# ESP01S.net
KiCad netlist of a schematic drawn in Altium Designer
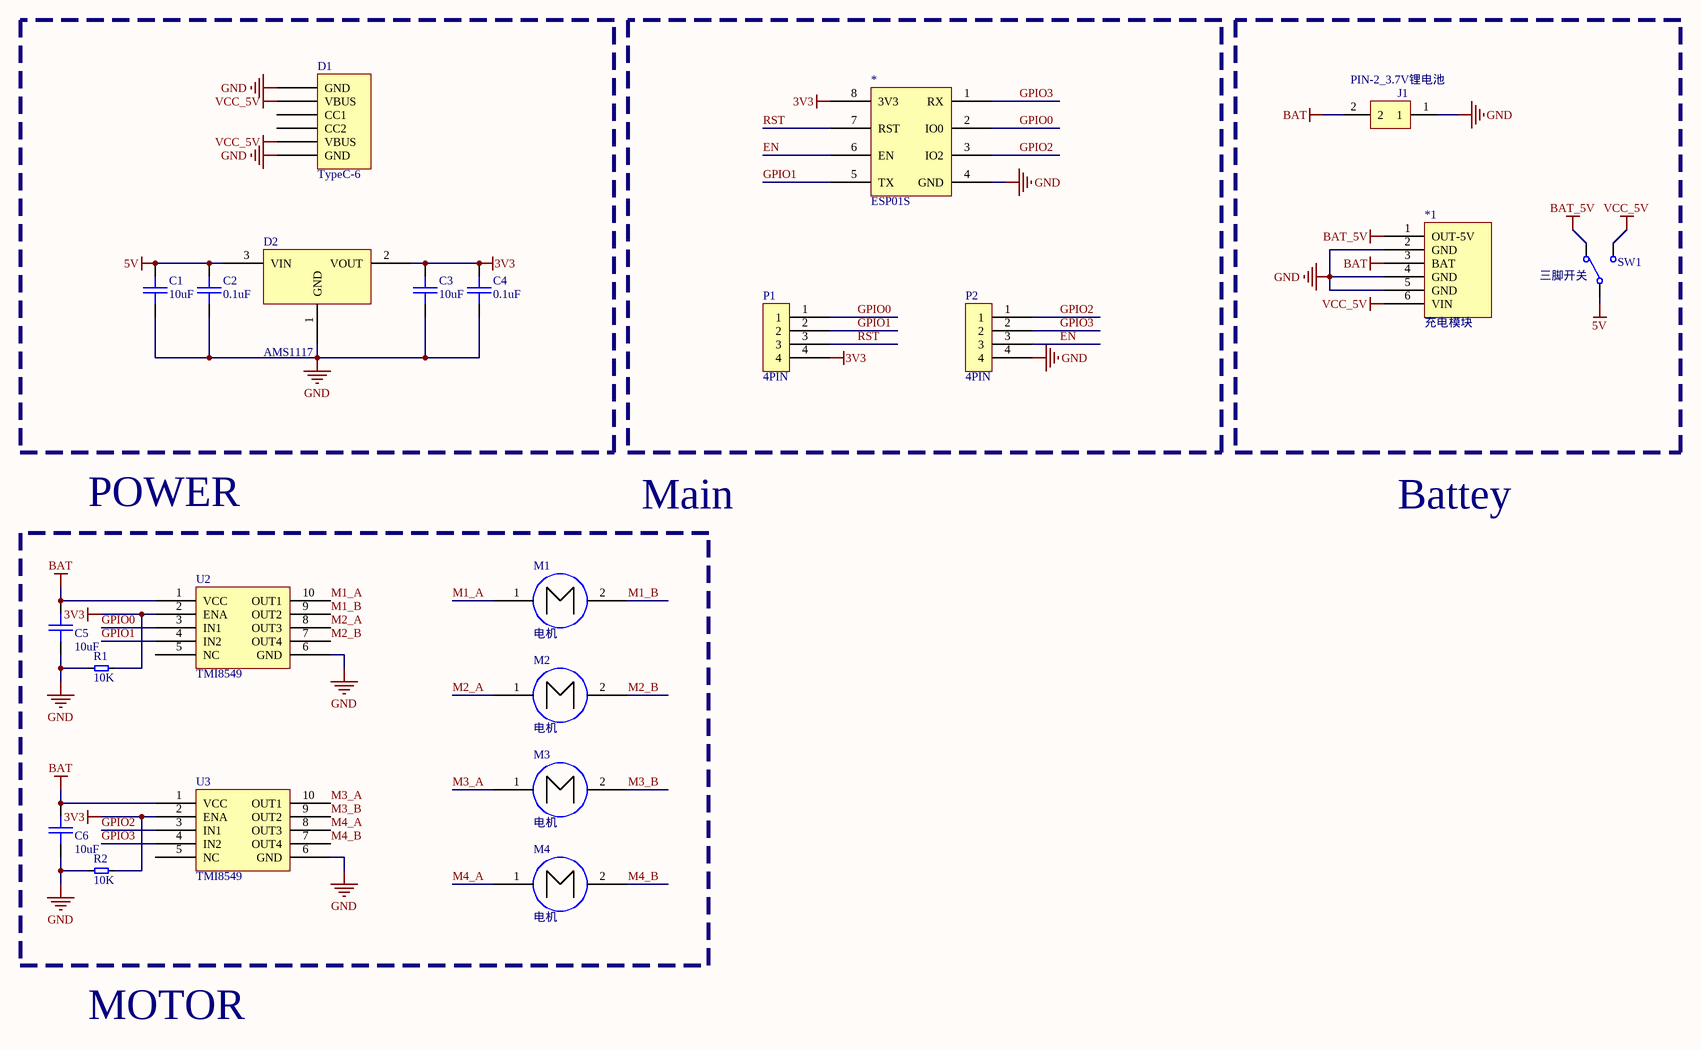
[diagram p0: ESP01S麦轮.SchDoc]

(export (version "E")
  (design (tool "Eeschema 10.0.6"))
  (components
    (comp (ref "*") (value "ESP01S") (footprint "2*4排针") (libsource (lib "ESP01S_OLED") (part "ESP01S")))
    (comp (ref "*1") (value "充电模块") (footprint "1*6排针") (libsource (lib "ESP01S_OLED") (part "充电模块")))
    (comp (ref "C1") (value "10uF") (footprint "0603C") (libsource (lib "XFuture") (part "CAP")))
    (comp (ref "C2") (value "0.1uF") (footprint "0603C") (libsource (lib "XFuture") (part "CAP")))
    (comp (ref "C3") (value "10uF") (footprint "0603C") (libsource (lib "XFuture") (part "CAP")))
    (comp (ref "C4") (value "0.1uF") (footprint "0603C") (libsource (lib "XFuture") (part "CAP")))
    (comp (ref "C5") (value "10uF") (footprint "0603C") (libsource (lib "XFuture") (part "CAP")))
    (comp (ref "C6") (value "10uF") (footprint "0603C") (libsource (lib "XFuture") (part "CAP")))
    (comp (ref "D1") (value "TypeC-6") (footprint "TypeC-6") (libsource (lib "ESP01S_OLED") (part "TypeC-6")))
    (comp (ref "D2") (value "AMS1117") (footprint "AMS1117") (libsource (lib "ESP01S_OLED") (part "AMS1117")))
    (comp (ref "J1") (value "PIN-2_3.7V锂电池") (footprint "XH2.54_2PIN") (libsource (lib "接插件") (part "PIN-2")))
    (comp (ref "M1") (value "电机") (footprint "电机触点") (libsource (lib "XFuture") (part "电机")))
    (comp (ref "M2") (value "电机") (footprint "电机触点") (libsource (lib "XFuture") (part "电机")))
    (comp (ref "M3") (value "电机") (footprint "电机触点") (libsource (lib "XFuture") (part "电机")))
    (comp (ref "M4") (value "电机") (footprint "电机触点") (libsource (lib "XFuture") (part "电机")))
    (comp (ref "P1") (value "4PIN") (footprint "1*4排针") (libsource (lib "XFuture") (part "4PIN")))
    (comp (ref "P2") (value "4PIN") (footprint "1*4排针") (libsource (lib "XFuture") (part "4PIN")))
    (comp (ref "R1") (value "10K") (footprint "0603C") (libsource (lib "XFuture") (part "RES")))
    (comp (ref "R2") (value "10K") (footprint "0603C") (libsource (lib "XFuture") (part "RES")))
    (comp (ref "SW1")
      (value "三脚开关")
      (footprint "1*3排针")
      (description "Switch")
      (libsource (lib "General") (part "SWITCH-NKK-M201x"))
    )
    (comp (ref "U2") (value "TMI8549") (footprint "SOP-10") (libsource (lib "XFuture") (part "TMI8529")))
    (comp (ref "U3") (value "TMI8549") (footprint "SOP-10") (libsource (lib "XFuture") (part "TMI8529")))
  )
  (nets
    (net (code "1") (name "/EN") (class "Default")
      (node (ref "*") (pin "6") (pinfunction "EN_6") (pintype "passive"))
      (node (ref "P2") (pin "3") (pinfunction "3_3") (pintype "passive"))
    )
    (net (code "2") (name "/GPIO0") (class "Default")
      (node (ref "*") (pin "2") (pinfunction "IO0_2") (pintype "passive"))
      (node (ref "P1") (pin "1") (pinfunction "1_1") (pintype "passive"))
      (node (ref "U2") (pin "3") (pinfunction "IN1_3") (pintype "passive"))
    )
    (net (code "3") (name "/GPIO1") (class "Default")
      (node (ref "*") (pin "5") (pinfunction "TX_5") (pintype "passive"))
      (node (ref "P1") (pin "2") (pinfunction "2_2") (pintype "passive"))
      (node (ref "U2") (pin "4") (pinfunction "IN2_4") (pintype "passive"))
    )
    (net (code "4") (name "/GPIO2") (class "Default")
      (node (ref "*") (pin "3") (pinfunction "IO2_3") (pintype "passive"))
      (node (ref "P2") (pin "1") (pinfunction "1_1") (pintype "passive"))
      (node (ref "U3") (pin "3") (pinfunction "IN1_3") (pintype "passive"))
    )
    (net (code "5") (name "/GPIO3") (class "Default")
      (node (ref "*") (pin "1") (pinfunction "RX_1") (pintype "passive"))
      (node (ref "P2") (pin "2") (pinfunction "2_2") (pintype "passive"))
      (node (ref "U3") (pin "4") (pinfunction "IN2_4") (pintype "passive"))
    )
    (net (code "6") (name "/M1_A") (class "Default")
      (node (ref "M1") (pin "1") (pinfunction "1_1") (pintype "passive"))
      (node (ref "U2") (pin "10") (pinfunction "OUT1_10") (pintype "passive"))
    )
    (net (code "7") (name "/M1_B") (class "Default")
      (node (ref "M1") (pin "2") (pinfunction "2_2") (pintype "passive"))
      (node (ref "U2") (pin "9") (pinfunction "OUT2_9") (pintype "passive"))
    )
    (net (code "8") (name "/M2_A") (class "Default")
      (node (ref "M2") (pin "1") (pinfunction "1_1") (pintype "passive"))
      (node (ref "U2") (pin "8") (pinfunction "OUT3_8") (pintype "passive"))
    )
    (net (code "9") (name "/M2_B") (class "Default")
      (node (ref "M2") (pin "2") (pinfunction "2_2") (pintype "passive"))
      (node (ref "U2") (pin "7") (pinfunction "OUT4_7") (pintype "passive"))
    )
    (net (code "10") (name "/M3_A") (class "Default")
      (node (ref "M3") (pin "1") (pinfunction "1_1") (pintype "passive"))
      (node (ref "U3") (pin "10") (pinfunction "OUT1_10") (pintype "passive"))
    )
    (net (code "11") (name "/M3_B") (class "Default")
      (node (ref "M3") (pin "2") (pinfunction "2_2") (pintype "passive"))
      (node (ref "U3") (pin "9") (pinfunction "OUT2_9") (pintype "passive"))
    )
    (net (code "12") (name "/M4_A") (class "Default")
      (node (ref "M4") (pin "1") (pinfunction "1_1") (pintype "passive"))
      (node (ref "U3") (pin "8") (pinfunction "OUT3_8") (pintype "passive"))
    )
    (net (code "13") (name "/M4_B") (class "Default")
      (node (ref "M4") (pin "2") (pinfunction "2_2") (pintype "passive"))
      (node (ref "U3") (pin "7") (pinfunction "OUT4_7") (pintype "passive"))
    )
    (net (code "14") (name "/RST") (class "Default")
      (node (ref "*") (pin "7") (pinfunction "RST_7") (pintype "passive"))
      (node (ref "P1") (pin "3") (pinfunction "3_3") (pintype "passive"))
    )
    (net (code "15") (name "3V3") (class "Default")
      (node (ref "*") (pin "8") (pinfunction "3V3_8") (pintype "passive"))
      (node (ref "C3") (pin "1") (pinfunction "1_1") (pintype "passive"))
      (node (ref "C4") (pin "1") (pinfunction "1_1") (pintype "passive"))
      (node (ref "D2") (pin "2") (pinfunction "VOUT_2") (pintype "passive"))
      (node (ref "P1") (pin "4") (pinfunction "4_4") (pintype "passive"))
      (node (ref "R1") (pin "2") (pinfunction "2_2") (pintype "passive"))
      (node (ref "R2") (pin "2") (pinfunction "2_2") (pintype "passive"))
      (node (ref "U2") (pin "2") (pinfunction "ENA_2") (pintype "passive"))
      (node (ref "U3") (pin "2") (pinfunction "ENA_2") (pintype "passive"))
    )
    (net (code "16") (name "5V") (class "Default")
      (node (ref "C1") (pin "1") (pinfunction "1_1") (pintype "passive"))
      (node (ref "C2") (pin "1") (pinfunction "1_1") (pintype "passive"))
      (node (ref "D2") (pin "3") (pinfunction "VIN_3") (pintype "passive"))
      (node (ref "SW1") (pin "2") (pinfunction "2_2") (pintype "passive"))
    )
    (net (code "17") (name "BAT") (class "Default")
      (node (ref "*1") (pin "3") (pinfunction "BAT_3") (pintype "passive"))
      (node (ref "C5") (pin "1") (pinfunction "1_1") (pintype "passive"))
      (node (ref "C6") (pin "1") (pinfunction "1_1") (pintype "passive"))
      (node (ref "J1") (pin "2") (pinfunction "2_2") (pintype "passive"))
      (node (ref "U2") (pin "1") (pinfunction "VCC_1") (pintype "passive"))
      (node (ref "U3") (pin "1") (pinfunction "VCC_1") (pintype "passive"))
    )
    (net (code "18") (name "BAT_5V") (class "Default")
      (node (ref "*1") (pin "1") (pinfunction "OUT-5V_1") (pintype "passive"))
      (node (ref "SW1") (pin "1") (pinfunction "1_1") (pintype "passive"))
    )
    (net (code "19") (name "GND") (class "Default")
      (node (ref "*") (pin "4") (pinfunction "GND_4") (pintype "passive"))
      (node (ref "*1") (pin "2") (pinfunction "GND_2") (pintype "passive"))
      (node (ref "*1") (pin "4") (pinfunction "GND_4") (pintype "passive"))
      (node (ref "*1") (pin "5") (pinfunction "GND_5") (pintype "passive"))
      (node (ref "C1") (pin "2") (pinfunction "2_2") (pintype "passive"))
      (node (ref "C2") (pin "2") (pinfunction "2_2") (pintype "passive"))
      (node (ref "C3") (pin "2") (pinfunction "2_2") (pintype "passive"))
      (node (ref "C4") (pin "2") (pinfunction "2_2") (pintype "passive"))
      (node (ref "C5") (pin "2") (pinfunction "2_2") (pintype "passive"))
      (node (ref "C6") (pin "2") (pinfunction "2_2") (pintype "passive"))
      (node (ref "D1") (pin "A12") (pinfunction "GND_A12") (pintype "passive"))
      (node (ref "D1") (pin "B12") (pinfunction "GND_B12") (pintype "passive"))
      (node (ref "D2") (pin "1") (pinfunction "GND_1") (pintype "passive"))
      (node (ref "J1") (pin "1") (pinfunction "1_1") (pintype "passive"))
      (node (ref "P2") (pin "4") (pinfunction "4_4") (pintype "passive"))
      (node (ref "R1") (pin "1") (pinfunction "1_1") (pintype "passive"))
      (node (ref "R2") (pin "1") (pinfunction "1_1") (pintype "passive"))
      (node (ref "U2") (pin "6") (pinfunction "GND_6") (pintype "passive"))
      (node (ref "U3") (pin "6") (pinfunction "GND_6") (pintype "passive"))
    )
    (net (code "20") (name "VCC_5V") (class "Default")
      (node (ref "*1") (pin "6") (pinfunction "VIN_6") (pintype "passive"))
      (node (ref "D1") (pin "A9") (pinfunction "VBUS_A9") (pintype "passive"))
      (node (ref "D1") (pin "B9") (pinfunction "VBUS_B9") (pintype "passive"))
      (node (ref "SW1") (pin "3") (pinfunction "3_3") (pintype "passive"))
    )
    (net (code "21") (name "unconnected-(D1-CC1-PadA5)") (class "Default")
      (node (ref "D1") (pin "A5") (pinfunction "CC1_A5") (pintype "passive"))
    )
    (net (code "22") (name "unconnected-(D1-CC2-PadB5)") (class "Default")
      (node (ref "D1") (pin "B5") (pinfunction "CC2_B5") (pintype "passive"))
    )
    (net (code "23") (name "unconnected-(U2-NC-Pad5)") (class "Default")
      (node (ref "U2") (pin "5") (pinfunction "NC_5") (pintype "passive"))
    )
    (net (code "24") (name "unconnected-(U3-NC-Pad5)") (class "Default")
      (node (ref "U3") (pin "5") (pinfunction "NC_5") (pintype "passive"))
    )
  )
)
